# DM3390_USB.net
KiCad netlist of a schematic drawn in Altium Designer
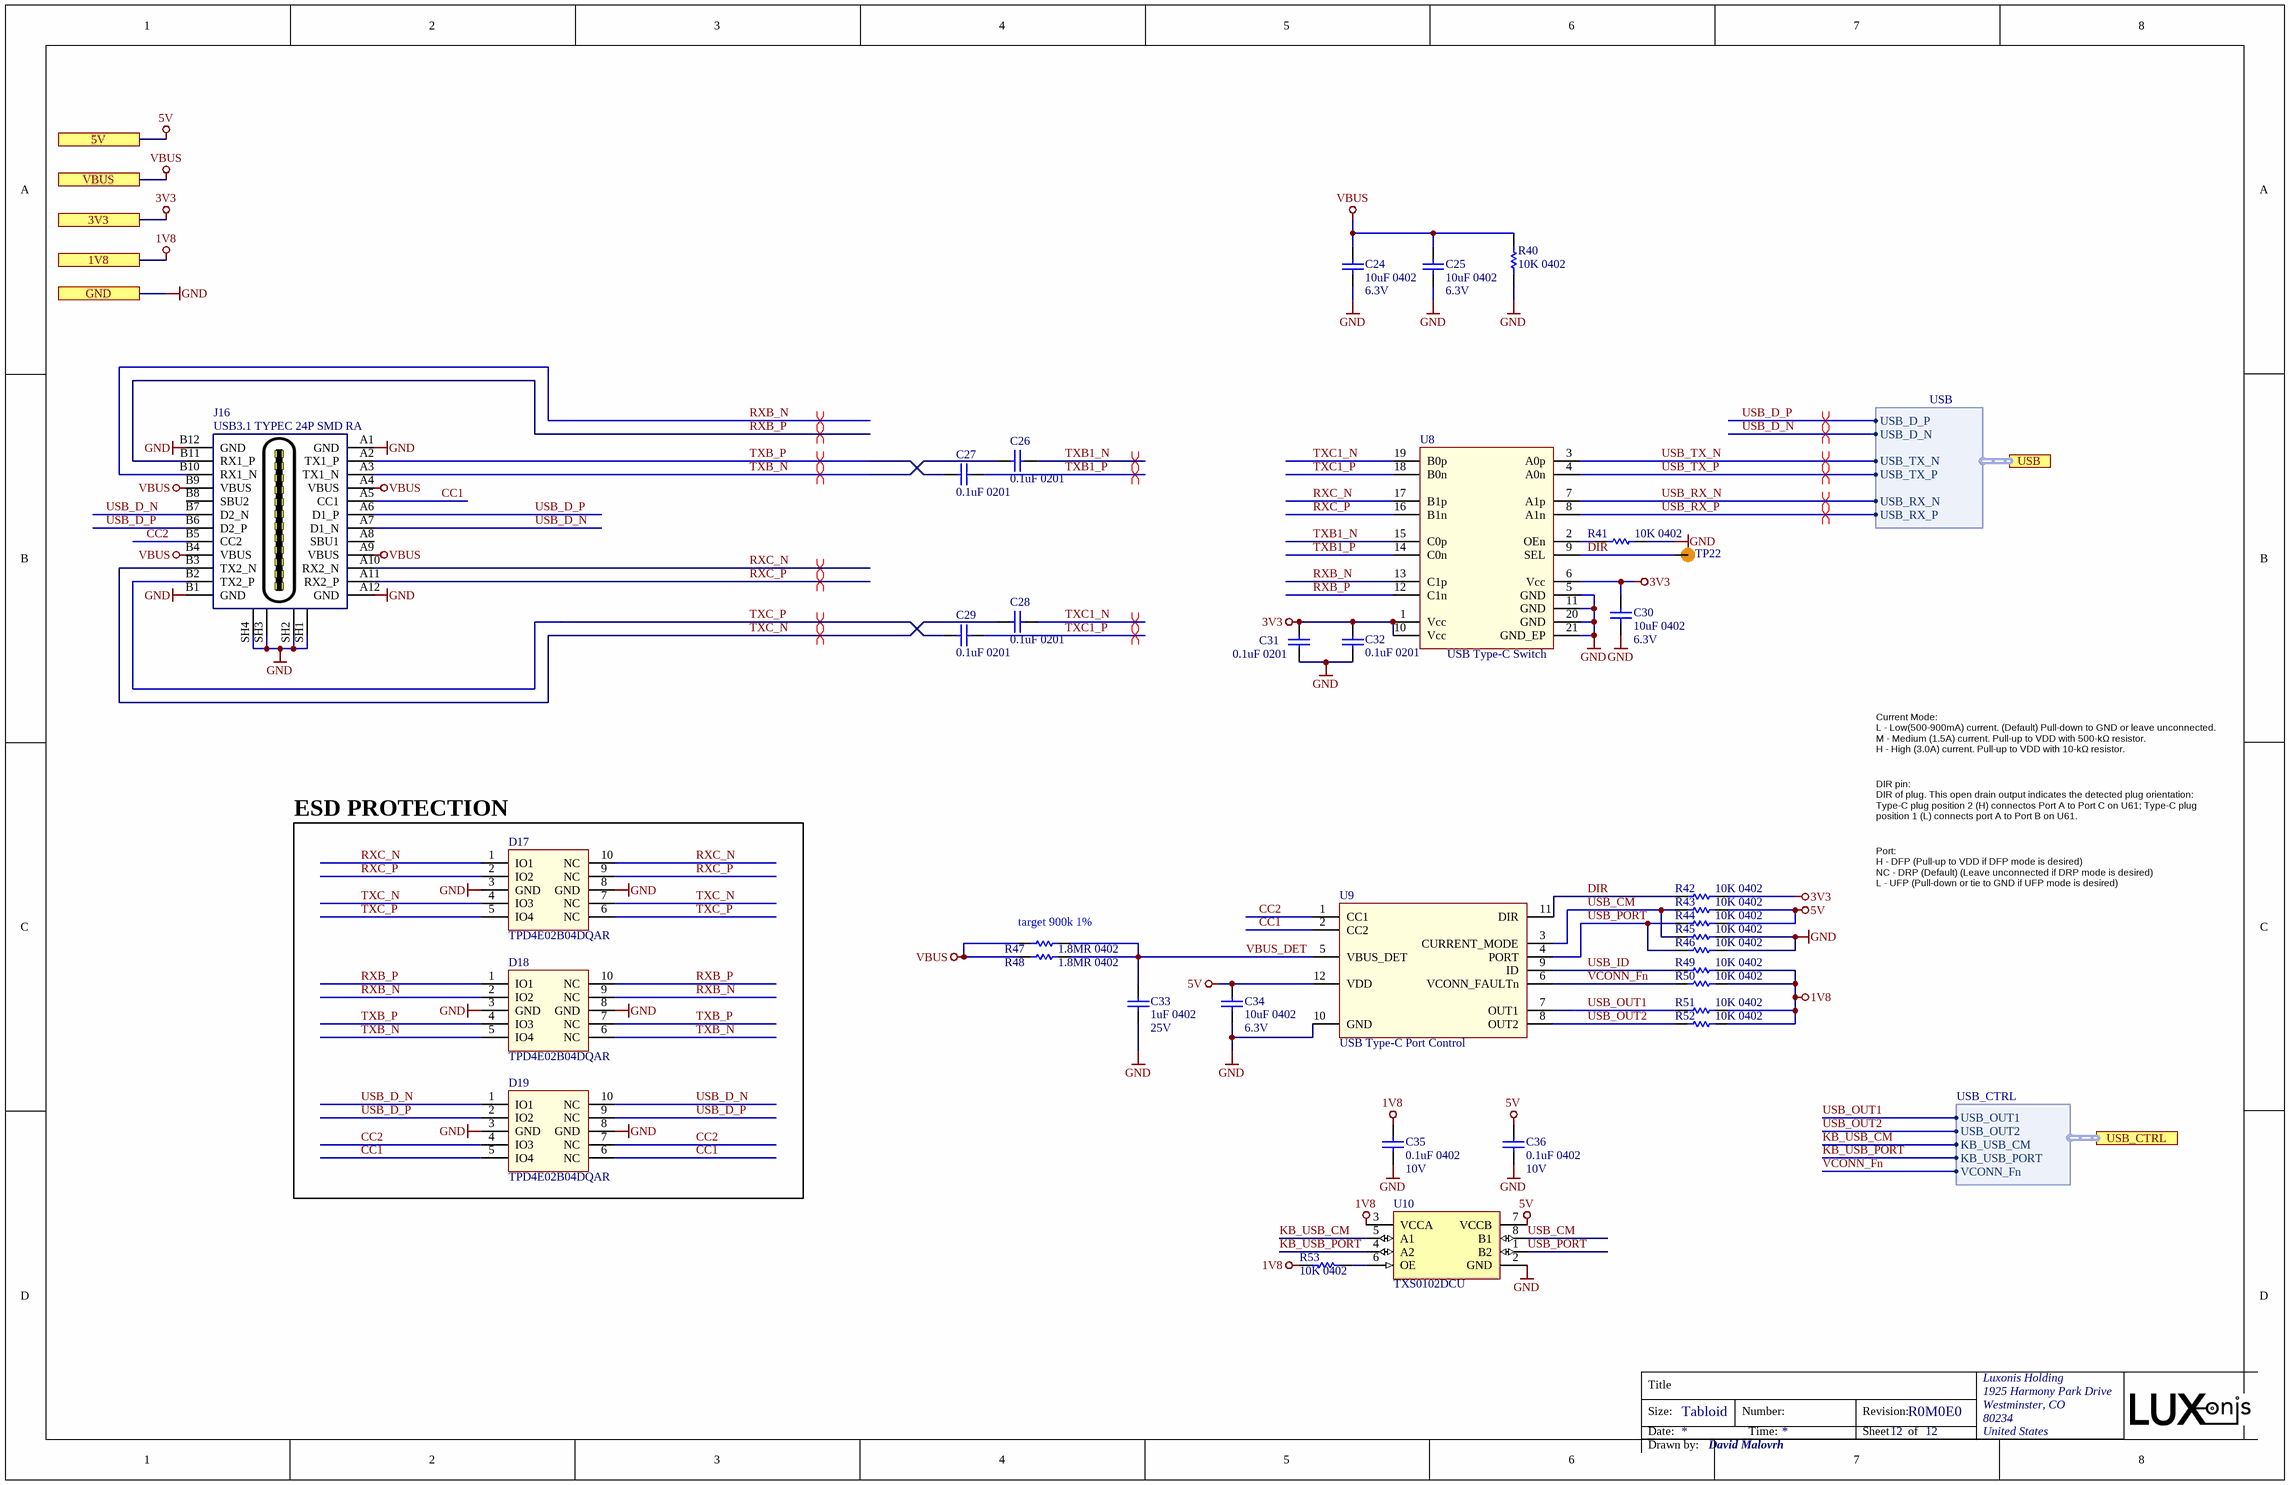
[diagram p0: DM3390_USB.SchDoc]

(export (version "E")
  (design (tool "Eeschema 10.0.6"))
  (components
    (comp (ref "C24")
      (value "10uF 0402")
      (footprint "CAP_Altium_Vault_Generic:CAPC0402(1005)70_N")
      (description "CAP CER 10UF 6.3V X5R 0402 20%")
      (fields (field (name "TOLERANCE") "20%") (field (name "VOLTAGE RATING") "6.3V"))
      (libsource (lib "LuxonisMaster") (part "GRM155R60J106ME15D"))
    )
    (comp (ref "C25")
      (value "10uF 0402")
      (footprint "CAP_Altium_Vault_Generic:CAPC0402(1005)70_N")
      (description "CAP CER 10UF 6.3V X5R 0402 20%")
      (fields (field (name "TOLERANCE") "20%") (field (name "VOLTAGE RATING") "6.3V"))
      (libsource (lib "LuxonisMaster") (part "GRM155R60J106ME15D"))
    )
    (comp (ref "C26")
      (value "0.1uF 0201")
      (footprint "CAP_Altium_Vault_Generic:CAPC0201(0603)33_L")
      (description "CAP CER 0.1UF 10V X5R 0201")
      (fields (field (name "TOLERANCE") "10%") (field (name "VOLTAGE") "10V"))
      (libsource (lib "LuxonisMaster") (part "GRM033R61A104KE15D"))
    )
    (comp (ref "C27")
      (value "0.1uF 0201")
      (footprint "CAP_Altium_Vault_Generic:CAPC0201(0603)33_L")
      (description "CAP CER 0.1UF 10V X5R 0201")
      (fields (field (name "TOLERANCE") "10%") (field (name "VOLTAGE") "10V"))
      (libsource (lib "LuxonisMaster") (part "GRM033R61A104KE15D"))
    )
    (comp (ref "C28")
      (value "0.1uF 0201")
      (footprint "CAP_Altium_Vault_Generic:CAPC0201(0603)33_L")
      (description "CAP CER 0.1UF 10V X5R 0201")
      (fields (field (name "TOLERANCE") "10%") (field (name "VOLTAGE") "10V"))
      (libsource (lib "LuxonisMaster") (part "GRM033R61A104KE15D"))
    )
    (comp (ref "C29")
      (value "0.1uF 0201")
      (footprint "CAP_Altium_Vault_Generic:CAPC0201(0603)33_L")
      (description "CAP CER 0.1UF 10V X5R 0201")
      (fields (field (name "TOLERANCE") "10%") (field (name "VOLTAGE") "10V"))
      (libsource (lib "LuxonisMaster") (part "GRM033R61A104KE15D"))
    )
    (comp (ref "C30")
      (value "10uF 0402")
      (footprint "CAP_Altium_Vault_Generic:CAPC0402(1005)70_N")
      (description "CAP CER 10UF 6.3V X5R 0402 20%")
      (fields (field (name "TOLERANCE") "20%") (field (name "VOLTAGE RATING") "6.3V"))
      (libsource (lib "LuxonisMaster") (part "GRM155R60J106ME15D"))
    )
    (comp (ref "C31")
      (value "0.1uF 0201")
      (footprint "CAP_Altium_Vault_Generic:CAPC0201(0603)33_L")
      (description "CAP CER 0.1UF 10V X5R 0201")
      (fields (field (name "TOLERANCE") "10%") (field (name "VOLTAGE") "10V"))
      (libsource (lib "LuxonisMaster") (part "GRM033R61A104KE15D"))
    )
    (comp (ref "C32")
      (value "0.1uF 0201")
      (footprint "CAP_Altium_Vault_Generic:CAPC0201(0603)33_L")
      (description "CAP CER 0.1UF 10V X5R 0201")
      (fields (field (name "TOLERANCE") "10%") (field (name "VOLTAGE") "10V"))
      (libsource (lib "LuxonisMaster") (part "GRM033R61A104KE15D"))
    )
    (comp (ref "C33")
      (value "1uF 0402")
      (footprint "CAP_Altium_Vault_Generic:CAPC0402(1005)70_L")
      (description "CAP CER 1UF 25V X5R 0402 10%")
      (fields
        (field (name "TOLERANCE") "10%")
        (field (name "VOLTAGE") "25V")
        (field (name "VOLTAGE RATING") "25V")
      )
      (libsource (lib "LuxonisMaster") (part "GRM155R61E105KA12D"))
    )
    (comp (ref "C34")
      (value "10uF 0402")
      (footprint "CAP_Altium_Vault_Generic:CAPC0402(1005)70_L")
      (description "CAP CER 10UF 6.3V X5R 0402 20%")
      (fields (field (name "TOLERANCE") "20%") (field (name "VOLTAGE RATING") "6.3V"))
      (libsource (lib "LuxonisMaster") (part "GRM155R60J106ME15D"))
    )
    (comp (ref "C35")
      (value "0.1uF 0402")
      (footprint "CAP_Altium_Vault_Generic:CAPC0402(1005)70_L")
      (description "CAP CER 0.1UF 10V X7R 0402 5%")
      (fields (field (name "TOLERANCE") "5%") (field (name "VOLTAGE RATING") "10V"))
      (libsource (lib "LuxonisMaster") (part "GRM155R71A104JA01D"))
    )
    (comp (ref "C36")
      (value "0.1uF 0402")
      (footprint "CAP_Altium_Vault_Generic:CAPC0402(1005)70_L")
      (description "CAP CER 0.1UF 10V X7R 0402 5%")
      (fields (field (name "TOLERANCE") "5%") (field (name "VOLTAGE RATING") "10V"))
      (libsource (lib "LuxonisMaster") (part "GRM155R71A104JA01D"))
    )
    (comp (ref "D17")
      (value "TPD4E02B04DQAR")
      (footprint "TPD4E02B04DQAR")
      (libsource (lib "LuxonisMaster") (part "TPD4E02B04DQAR"))
    )
    (comp (ref "D18")
      (value "TPD4E02B04DQAR")
      (footprint "TPD4E02B04DQAR")
      (libsource (lib "LuxonisMaster") (part "TPD4E02B04DQAR"))
    )
    (comp (ref "D19")
      (value "TPD4E02B04DQAR")
      (footprint "TPD4E02B04DQAR")
      (libsource (lib "LuxonisMaster") (part "TPD4E02B04DQAR"))
    )
    (comp (ref "J16")
      (value "USB3.1 TYPEC 24P SMD RA")
      (footprint "LuxonisMaster:105450-0101")
      (description "CONN RCP USB3.1 TYPEC 24P SMD RA")
      (libsource (lib "LuxonisMaster") (part "105450-0101"))
    )
    (comp (ref "R40")
      (value "10K 0402")
      (footprint "RES_Altium_Vault_Generic:RESC0402(1005)_N")
      (fields (field (name "TOLERANCE") "1%"))
      (libsource (lib "LuxonisMaster") (part "RC0402FR-1310KL"))
    )
    (comp (ref "R41")
      (value "10K 0402")
      (footprint "RES_Altium_Vault_Generic:RESC0402(1005)_N")
      (fields (field (name "TOLERANCE") "1%"))
      (libsource (lib "LuxonisMaster") (part "RC0402FR-1310KL"))
    )
    (comp (ref "R42")
      (value "10K 0402")
      (footprint "RES_Altium_Vault_Generic:RESC0402(1005)_L")
      (fields (field (name "TOLERANCE") "1%"))
      (libsource (lib "LuxonisMaster") (part "RC0402FR-1310KL"))
    )
    (comp (ref "R43")
      (value "10K 0402")
      (footprint "RES_Altium_Vault_Generic:RESC0402(1005)_L")
      (fields (field (name "TOLERANCE") "1%"))
      (libsource (lib "LuxonisMaster") (part "RC0402FR-1310KL"))
    )
    (comp (ref "R44")
      (value "10K 0402")
      (footprint "RES_Altium_Vault_Generic:RESC0402(1005)_L")
      (fields (field (name "TOLERANCE") "1%"))
      (libsource (lib "LuxonisMaster") (part "RC0402FR-1310KL"))
    )
    (comp (ref "R45")
      (value "10K 0402")
      (footprint "RES_Altium_Vault_Generic:RESC0402(1005)_L")
      (fields (field (name "TOLERANCE") "1%"))
      (libsource (lib "LuxonisMaster") (part "RC0402FR-1310KL"))
    )
    (comp (ref "R46")
      (value "10K 0402")
      (footprint "RES_Altium_Vault_Generic:RESC0402(1005)_L")
      (fields (field (name "TOLERANCE") "1%"))
      (libsource (lib "LuxonisMaster") (part "RC0402FR-1310KL"))
    )
    (comp (ref "R47")
      (value "1.8MR 0402")
      (footprint "RES_Altium_Vault_Generic:RESC0402(1005)_L")
      (description "RES SMD 1.8M OHM 1% 1/16W 0402")
      (fields (field (name "TOLERANCE") "1%"))
      (libsource (lib "LuxonisMaster") (part "CRCW04021M80FKED"))
    )
    (comp (ref "R48")
      (value "1.8MR 0402")
      (footprint "RES_Altium_Vault_Generic:RESC0402(1005)_L")
      (description "RES SMD 1.8M OHM 1% 1/16W 0402")
      (fields (field (name "TOLERANCE") "1%"))
      (libsource (lib "LuxonisMaster") (part "CRCW04021M80FKED"))
    )
    (comp (ref "R49")
      (value "10K 0402")
      (footprint "RES_Altium_Vault_Generic:RESC0402(1005)_L")
      (fields (field (name "TOLERANCE") "1%"))
      (libsource (lib "LuxonisMaster") (part "RC0402FR-1310KL"))
    )
    (comp (ref "R50")
      (value "10K 0402")
      (footprint "RES_Altium_Vault_Generic:RESC0402(1005)_L")
      (fields (field (name "TOLERANCE") "1%"))
      (libsource (lib "LuxonisMaster") (part "RC0402FR-1310KL"))
    )
    (comp (ref "R51")
      (value "10K 0402")
      (footprint "RES_Altium_Vault_Generic:RESC0402(1005)_L")
      (fields (field (name "TOLERANCE") "1%"))
      (libsource (lib "LuxonisMaster") (part "RC0402FR-1310KL"))
    )
    (comp (ref "R52")
      (value "10K 0402")
      (footprint "RES_Altium_Vault_Generic:RESC0402(1005)_L")
      (fields (field (name "TOLERANCE") "1%"))
      (libsource (lib "LuxonisMaster") (part "RC0402FR-1310KL"))
    )
    (comp (ref "R53")
      (value "10K 0402")
      (footprint "RES_Altium_Vault_Generic:RESC0402(1005)_N")
      (fields (field (name "TOLERANCE") "1%"))
      (libsource (lib "LuxonisMaster") (part "RC0402FR-1310KL"))
    )
    (comp (ref "TP22")
      (value "TP100_200_NS")
      (footprint "LuxonisMaster:TP100_200_NS")
      (libsource (lib "LuxonisMaster") (part "TEST_POINT"))
    )
    (comp (ref "U8")
      (value "USB Type-C Switch")
      (footprint "CBTL02043A")
      (libsource (lib "LuxonisMaster") (part "CBTL02043A"))
    )
    (comp (ref "U9")
      (value "USB Type-C Port Control")
      (footprint "LuxonisMaster:TUSB321RWBR")
      (description "IC USB PORT CONTROL TYPE-C 12X2Q")
      (libsource (lib "LuxonisMaster") (part "TUSB321RWBR"))
    )
    (comp (ref "U10")
      (value "TXS0102DCU")
      (footprint "TXS0102DCUR")
      (description "TEXAS INSTRUMENTS - TXS0102DCUR - IC, TRANSLATOR, 2 BIT, BI, US-8")
      (libsource (lib "LuxonisMaster") (part "TXS0102DCUR"))
    )
  )
  (nets
    (net (code "3") (name "/CC1") (class "Default")
      (node (ref "D19") (pin "5") (pinfunction "IO4_5") (pintype "passive"))
      (node (ref "D19") (pin "6") (pinfunction "NC_6") (pintype "passive"))
      (node (ref "J16") (pin "A5") (pinfunction "CC1_A5") (pintype "passive"))
      (node (ref "U9") (pin "2") (pinfunction "CC2_2") (pintype "passive"))
    )
    (net (code "4") (name "/CC2") (class "Default")
      (node (ref "D19") (pin "4") (pinfunction "IO3_4") (pintype "passive"))
      (node (ref "D19") (pin "7") (pinfunction "NC_7") (pintype "passive"))
      (node (ref "J16") (pin "B5") (pinfunction "CC2_B5") (pintype "passive"))
      (node (ref "U9") (pin "1") (pinfunction "CC1_1") (pintype "passive"))
    )
    (net (code "5") (name "/DIR") (class "Default")
      (node (ref "R42") (pin "1") (pinfunction "1_1") (pintype "passive"))
      (node (ref "TP22") (pin "1") (pintype "passive"))
      (node (ref "U8") (pin "9") (pinfunction "SEL_9") (pintype "passive"))
      (node (ref "U9") (pin "11") (pinfunction "DIR_11") (pintype "passive"))
    )
    (net (code "6") (name "/KB_USB_CM") (class "Default")
      (node (ref "U10") (pin "5") (pinfunction "A1_5") (pintype "bidirectional"))
    )
    (net (code "7") (name "/KB_USB_PORT") (class "Default")
      (node (ref "U10") (pin "4") (pinfunction "A2_4") (pintype "bidirectional"))
    )
    (net (code "8") (name "/RXB_N") (class "Default")
      (node (ref "D18") (pin "2") (pinfunction "IO2_2") (pintype "passive"))
      (node (ref "D18") (pin "9") (pinfunction "NC_9") (pintype "passive"))
      (node (ref "J16") (pin "B10") (pinfunction "RX1_N_B10") (pintype "passive"))
      (node (ref "U8") (pin "13") (pinfunction "C1p_13") (pintype "passive"))
    )
    (net (code "9") (name "/RXB_P") (class "Default")
      (node (ref "D18") (pin "1") (pinfunction "IO1_1") (pintype "passive"))
      (node (ref "D18") (pin "10") (pinfunction "NC_10") (pintype "passive"))
      (node (ref "J16") (pin "B11") (pinfunction "RX1_P_B11") (pintype "passive"))
      (node (ref "U8") (pin "12") (pinfunction "C1n_12") (pintype "passive"))
    )
    (net (code "10") (name "/RXC_N") (class "Default")
      (node (ref "D17") (pin "1") (pinfunction "IO1_1") (pintype "passive"))
      (node (ref "D17") (pin "10") (pinfunction "NC_10") (pintype "passive"))
      (node (ref "J16") (pin "A10") (pinfunction "RX2_N_A10") (pintype "passive"))
      (node (ref "U8") (pin "17") (pinfunction "B1p_17") (pintype "passive"))
    )
    (net (code "11") (name "/RXC_P") (class "Default")
      (node (ref "D17") (pin "2") (pinfunction "IO2_2") (pintype "passive"))
      (node (ref "D17") (pin "9") (pinfunction "NC_9") (pintype "passive"))
      (node (ref "J16") (pin "A11") (pinfunction "RX2_P_A11") (pintype "passive"))
      (node (ref "U8") (pin "16") (pinfunction "B1n_16") (pintype "passive"))
    )
    (net (code "12") (name "/TXB1_N") (class "Default")
      (node (ref "C26") (pin "2") (pinfunction "2_2") (pintype "passive"))
      (node (ref "U8") (pin "15") (pinfunction "C0p_15") (pintype "passive"))
    )
    (net (code "13") (name "/TXB1_P") (class "Default")
      (node (ref "C27") (pin "2") (pinfunction "2_2") (pintype "passive"))
      (node (ref "U8") (pin "14") (pinfunction "C0n_14") (pintype "passive"))
    )
    (net (code "14") (name "/TXB_N") (class "Default")
      (node (ref "C26") (pin "1") (pinfunction "1_1") (pintype "passive"))
      (node (ref "D18") (pin "5") (pinfunction "IO4_5") (pintype "passive"))
      (node (ref "D18") (pin "6") (pinfunction "NC_6") (pintype "passive"))
      (node (ref "J16") (pin "A3") (pinfunction "TX1_N_A3") (pintype "passive"))
    )
    (net (code "15") (name "/TXB_P") (class "Default")
      (node (ref "C27") (pin "1") (pinfunction "1_1") (pintype "passive"))
      (node (ref "D18") (pin "4") (pinfunction "IO3_4") (pintype "passive"))
      (node (ref "D18") (pin "7") (pinfunction "NC_7") (pintype "passive"))
      (node (ref "J16") (pin "A2") (pinfunction "TX1_P_A2") (pintype "passive"))
    )
    (net (code "16") (name "/TXC1_N") (class "Default")
      (node (ref "C28") (pin "2") (pinfunction "2_2") (pintype "passive"))
      (node (ref "U8") (pin "19") (pinfunction "B0p_19") (pintype "passive"))
    )
    (net (code "17") (name "/TXC1_P") (class "Default")
      (node (ref "C29") (pin "2") (pinfunction "2_2") (pintype "passive"))
      (node (ref "U8") (pin "18") (pinfunction "B0n_18") (pintype "passive"))
    )
    (net (code "18") (name "/TXC_N") (class "Default")
      (node (ref "C28") (pin "1") (pinfunction "1_1") (pintype "passive"))
      (node (ref "D17") (pin "4") (pinfunction "IO3_4") (pintype "passive"))
      (node (ref "D17") (pin "7") (pinfunction "NC_7") (pintype "passive"))
      (node (ref "J16") (pin "B3") (pinfunction "TX2_N_B3") (pintype "passive"))
    )
    (net (code "19") (name "/TXC_P") (class "Default")
      (node (ref "C29") (pin "1") (pinfunction "1_1") (pintype "passive"))
      (node (ref "D17") (pin "5") (pinfunction "IO4_5") (pintype "passive"))
      (node (ref "D17") (pin "6") (pinfunction "NC_6") (pintype "passive"))
      (node (ref "J16") (pin "B2") (pinfunction "TX2_P_B2") (pintype "passive"))
    )
    (net (code "20") (name "/USB_CM") (class "Default")
      (node (ref "R43") (pin "1") (pinfunction "1_1") (pintype "passive"))
      (node (ref "R45") (pin "1") (pinfunction "1_1") (pintype "passive"))
      (node (ref "U10") (pin "8") (pinfunction "B1_8") (pintype "bidirectional"))
      (node (ref "U9") (pin "3") (pinfunction "CURRENT_MODE_3") (pintype "passive"))
    )
    (net (code "21") (name "/USB_D_N") (class "Default")
      (node (ref "D19") (pin "1") (pinfunction "IO1_1") (pintype "passive"))
      (node (ref "D19") (pin "10") (pinfunction "NC_10") (pintype "passive"))
      (node (ref "J16") (pin "A7") (pinfunction "D1_N_A7") (pintype "passive"))
      (node (ref "J16") (pin "B7") (pinfunction "D2_N_B7") (pintype "passive"))
    )
    (net (code "22") (name "/USB_D_P") (class "Default")
      (node (ref "D19") (pin "2") (pinfunction "IO2_2") (pintype "passive"))
      (node (ref "D19") (pin "9") (pinfunction "NC_9") (pintype "passive"))
      (node (ref "J16") (pin "A6") (pinfunction "D1_P_A6") (pintype "passive"))
      (node (ref "J16") (pin "B6") (pinfunction "D2_P_B6") (pintype "passive"))
    )
    (net (code "23") (name "/USB_ID") (class "Default")
      (node (ref "R49") (pin "1") (pinfunction "1_1") (pintype "passive"))
      (node (ref "U9") (pin "9") (pinfunction "ID_9") (pintype "passive"))
    )
    (net (code "24") (name "/USB_OUT1") (class "Default")
      (node (ref "R51") (pin "1") (pinfunction "1_1") (pintype "passive"))
      (node (ref "U9") (pin "7") (pinfunction "OUT1_7") (pintype "passive"))
    )
    (net (code "25") (name "/USB_OUT2") (class "Default")
      (node (ref "R52") (pin "1") (pinfunction "1_1") (pintype "passive"))
      (node (ref "U9") (pin "8") (pinfunction "OUT2_8") (pintype "passive"))
    )
    (net (code "26") (name "/USB_PORT") (class "Default")
      (node (ref "R44") (pin "1") (pinfunction "1_1") (pintype "passive"))
      (node (ref "R46") (pin "1") (pinfunction "1_1") (pintype "passive"))
      (node (ref "U10") (pin "1") (pinfunction "B2_1") (pintype "bidirectional"))
      (node (ref "U9") (pin "4") (pinfunction "PORT_4") (pintype "passive"))
    )
    (net (code "27") (name "/USB_RX_N") (class "Default")
      (node (ref "U8") (pin "7") (pinfunction "A1p_7") (pintype "passive"))
    )
    (net (code "28") (name "/USB_RX_P") (class "Default")
      (node (ref "U8") (pin "8") (pinfunction "A1n_8") (pintype "passive"))
    )
    (net (code "29") (name "/USB_TX_N") (class "Default")
      (node (ref "U8") (pin "3") (pinfunction "A0p_3") (pintype "passive"))
    )
    (net (code "30") (name "/USB_TX_P") (class "Default")
      (node (ref "U8") (pin "4") (pinfunction "A0n_4") (pintype "passive"))
    )
    (net (code "31") (name "/VBUS_DET") (class "Default")
      (node (ref "C33") (pin "2") (pinfunction "2_2") (pintype "passive"))
      (node (ref "R47") (pin "2") (pinfunction "2_2") (pintype "passive"))
      (node (ref "R48") (pin "2") (pinfunction "2_2") (pintype "passive"))
      (node (ref "U9") (pin "5") (pinfunction "VBUS_DET_5") (pintype "passive"))
    )
    (net (code "32") (name "/VCONN_Fn") (class "Default")
      (node (ref "R50") (pin "1") (pinfunction "1_1") (pintype "passive"))
      (node (ref "U9") (pin "6") (pinfunction "VCONN_FAULTn_6") (pintype "passive"))
    )
    (net (code "35") (name "1V8") (class "Default")
      (node (ref "C35") (pin "2") (pinfunction "2_2") (pintype "passive"))
      (node (ref "R49") (pin "2") (pinfunction "2_2") (pintype "passive"))
      (node (ref "R50") (pin "2") (pinfunction "2_2") (pintype "passive"))
      (node (ref "R51") (pin "2") (pinfunction "2_2") (pintype "passive"))
      (node (ref "R52") (pin "2") (pinfunction "2_2") (pintype "passive"))
      (node (ref "R53") (pin "2") (pinfunction "2_2") (pintype "passive"))
      (node (ref "U10") (pin "3") (pinfunction "VCCA_3") (pintype "power_in"))
    )
    (net (code "36") (name "3V3") (class "Default")
      (node (ref "C30") (pin "2") (pinfunction "2_2") (pintype "passive"))
      (node (ref "C31") (pin "2") (pinfunction "2_2") (pintype "passive"))
      (node (ref "C32") (pin "2") (pinfunction "2_2") (pintype "passive"))
      (node (ref "R42") (pin "2") (pinfunction "2_2") (pintype "passive"))
      (node (ref "U8") (pin "1") (pinfunction "Vcc_1") (pintype "passive"))
      (node (ref "U8") (pin "10") (pinfunction "Vcc_10") (pintype "passive"))
      (node (ref "U8") (pin "6") (pinfunction "Vcc_6") (pintype "passive"))
    )
    (net (code "37") (name "5V") (class "Default")
      (node (ref "C34") (pin "2") (pinfunction "2_2") (pintype "passive"))
      (node (ref "C36") (pin "2") (pinfunction "2_2") (pintype "passive"))
      (node (ref "R43") (pin "2") (pinfunction "2_2") (pintype "passive"))
      (node (ref "R44") (pin "2") (pinfunction "2_2") (pintype "passive"))
      (node (ref "U10") (pin "7") (pinfunction "VCCB_7") (pintype "power_in"))
      (node (ref "U9") (pin "12") (pinfunction "VDD_12") (pintype "passive"))
    )
    (net (code "38") (name "GND") (class "Default")
      (node (ref "C24") (pin "1") (pinfunction "1_1") (pintype "passive"))
      (node (ref "C25") (pin "1") (pinfunction "1_1") (pintype "passive"))
      (node (ref "C30") (pin "1") (pinfunction "1_1") (pintype "passive"))
      (node (ref "C31") (pin "1") (pinfunction "1_1") (pintype "passive"))
      (node (ref "C32") (pin "1") (pinfunction "1_1") (pintype "passive"))
      (node (ref "C33") (pin "1") (pinfunction "1_1") (pintype "passive"))
      (node (ref "C34") (pin "1") (pinfunction "1_1") (pintype "passive"))
      (node (ref "C35") (pin "1") (pinfunction "1_1") (pintype "passive"))
      (node (ref "C36") (pin "1") (pinfunction "1_1") (pintype "passive"))
      (node (ref "D17") (pin "3") (pinfunction "GND_3") (pintype "passive"))
      (node (ref "D17") (pin "8") (pinfunction "GND_8") (pintype "passive"))
      (node (ref "D18") (pin "3") (pinfunction "GND_3") (pintype "passive"))
      (node (ref "D18") (pin "8") (pinfunction "GND_8") (pintype "passive"))
      (node (ref "D19") (pin "3") (pinfunction "GND_3") (pintype "passive"))
      (node (ref "D19") (pin "8") (pinfunction "GND_8") (pintype "passive"))
      (node (ref "J16") (pin "A1") (pinfunction "GND_A1") (pintype "passive"))
      (node (ref "J16") (pin "A12") (pinfunction "GND_A12") (pintype "passive"))
      (node (ref "J16") (pin "B1") (pinfunction "GND_B1") (pintype "passive"))
      (node (ref "J16") (pin "B12") (pinfunction "GND_B12") (pintype "passive"))
      (node (ref "J16") (pin "SH1") (pinfunction "SH_SH1") (pintype "passive"))
      (node (ref "J16") (pin "SH2") (pinfunction "SH_SH2") (pintype "passive"))
      (node (ref "J16") (pin "SH3") (pinfunction "SH_SH3") (pintype "passive"))
      (node (ref "J16") (pin "SH4") (pinfunction "SH_SH4") (pintype "passive"))
      (node (ref "R40") (pin "1") (pinfunction "1_1") (pintype "passive"))
      (node (ref "R41") (pin "2") (pinfunction "2_2") (pintype "passive"))
      (node (ref "R45") (pin "2") (pinfunction "2_2") (pintype "passive"))
      (node (ref "R46") (pin "2") (pinfunction "2_2") (pintype "passive"))
      (node (ref "U10") (pin "2") (pinfunction "GND_2") (pintype "power_in"))
      (node (ref "U8") (pin "11") (pinfunction "GND_11") (pintype "passive"))
      (node (ref "U8") (pin "20") (pinfunction "GND_20") (pintype "passive"))
      (node (ref "U8") (pin "21") (pinfunction "GND_EP_21") (pintype "passive"))
      (node (ref "U8") (pin "5") (pinfunction "GND_5") (pintype "passive"))
      (node (ref "U9") (pin "10") (pinfunction "GND_10") (pintype "passive"))
    )
    (net (code "39") (name "Net-(U8-OEn)") (class "Default")
      (node (ref "R41") (pin "1") (pinfunction "1_1") (pintype "passive"))
      (node (ref "U8") (pin "2") (pinfunction "OEn_2") (pintype "passive"))
    )
    (net (code "40") (name "Net-(U10-OE)") (class "Default")
      (node (ref "R53") (pin "1") (pinfunction "1_1") (pintype "passive"))
      (node (ref "U10") (pin "6") (pinfunction "OE_6") (pintype "input"))
    )
    (net (code "41") (name "VBUS") (class "Default")
      (node (ref "C24") (pin "2") (pinfunction "2_2") (pintype "passive"))
      (node (ref "C25") (pin "2") (pinfunction "2_2") (pintype "passive"))
      (node (ref "J16") (pin "A4") (pinfunction "VBUS_A4") (pintype "passive"))
      (node (ref "J16") (pin "A9") (pinfunction "VBUS_A9") (pintype "passive"))
      (node (ref "J16") (pin "B4") (pinfunction "VBUS_B4") (pintype "passive"))
      (node (ref "J16") (pin "B9") (pinfunction "VBUS_B9") (pintype "passive"))
      (node (ref "R40") (pin "2") (pinfunction "2_2") (pintype "passive"))
      (node (ref "R47") (pin "1") (pinfunction "1_1") (pintype "passive"))
      (node (ref "R48") (pin "1") (pinfunction "1_1") (pintype "passive"))
    )
    (net (code "42") (name "unconnected-(J16-SBU1-PadA8)") (class "Default")
      (node (ref "J16") (pin "A8") (pinfunction "SBU1_A8") (pintype "passive"))
    )
    (net (code "43") (name "unconnected-(J16-SBU2-PadB8)") (class "Default")
      (node (ref "J16") (pin "B8") (pinfunction "SBU2_B8") (pintype "passive"))
    )
  )
)
